# LEDShoeslaces.net
KiCad netlist of a schematic drawn in EAGLE
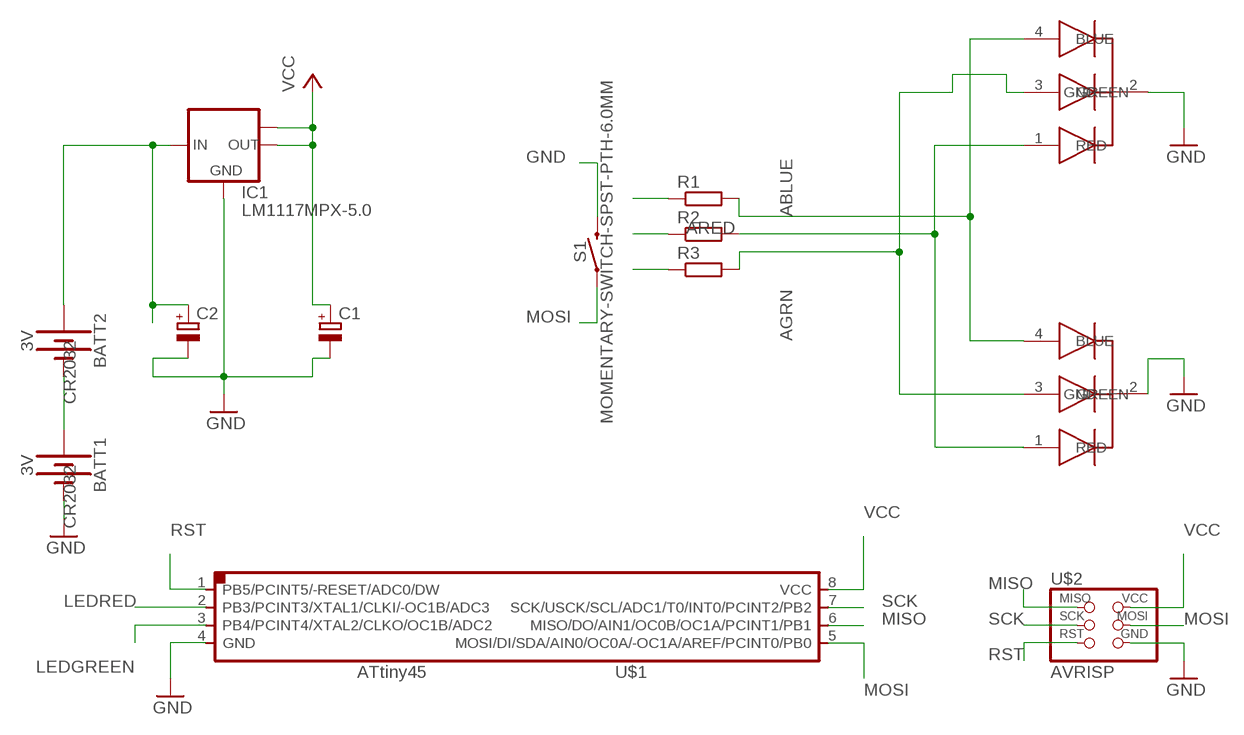
[diagram p0: schematic, sheet 1]

(export (version "E")
  (design (tool "Eeschema 10.0.6"))
  (components
    (comp (ref "BATT1")
      (value "3V")
      (footprint "eagle-import:BATTCON_20MM")
      (fields (field (name "PROD_ID") "BATT-11519") (field (name "PROD_ID_1") "CR2032"))
      (libsource (lib "eagle-import") (part "BATTERY-20MM_SMD"))
    )
    (comp (ref "BATT2")
      (value "3V")
      (footprint "eagle-import:BATTCON_20MM")
      (fields (field (name "PROD_ID") "BATT-11519") (field (name "PROD_ID_1") "CR2032"))
      (libsource (lib "eagle-import") (part "BATTERY-20MM_SMD"))
    )
    (comp (ref "C1")
      (value "CPOL-EUCT7343")
      (footprint "eagle-import:CT7343")
      (libsource (lib "eagle-import") (part "CPOL-EUCT7343"))
    )
    (comp (ref "C2")
      (value "CPOL-EUCT7343")
      (footprint "eagle-import:CT7343")
      (libsource (lib "eagle-import") (part "CPOL-EUCT7343"))
    )
    (comp (ref "IC1")
      (value "LM1117MPX-5.0")
      (footprint "eagle-import:SOT223")
      (libsource (lib "eagle-import") (part "LM1117MPX-5.0"))
    )
    (comp (ref "R1")
      (value "R-EU_R1206")
      (footprint "eagle-import:R1206")
      (libsource (lib "eagle-import") (part "R-EU_R1206"))
    )
    (comp (ref "R2")
      (value "R-EU_R1206")
      (footprint "eagle-import:R1206")
      (libsource (lib "eagle-import") (part "R-EU_R1206"))
    )
    (comp (ref "R3")
      (value "R-EU_R1206")
      (footprint "eagle-import:R1206")
      (libsource (lib "eagle-import") (part "R-EU_R1206"))
    )
    (comp (ref "S1")
      (value "MOMENTARY-SWITCH-SPST-PTH-6.0MM")
      (footprint "eagle-import:TACTILE_SWITCH_PTH_6.0MM")
      (libsource (lib "eagle-import") (part "MOMENTARY-SWITCH-SPST-PTH-6.0MM"))
    )
    (comp (ref "U$1")
      (value "ATTINY45SI")
      (footprint "eagle-import:SOIC8")
      (libsource (lib "eagle-import") (part "ATTINY45SI"))
    )
    (comp (ref "U$2")
      (value "AVRISP")
      (footprint "eagle-import:2X03")
      (libsource (lib "eagle-import") (part "AVRISP"))
    )
    (comp (ref "U$3")
      (value "LEDRGB")
      (footprint "eagle-import:LEDRGB")
      (libsource (lib "eagle-import") (part "LEDRGB"))
    )
    (comp (ref "U$4")
      (value "LEDRGB")
      (footprint "eagle-import:LEDRGB")
      (libsource (lib "eagle-import") (part "LEDRGB"))
    )
  )
  (nets
    (net (code "1") (name "/ABLUE") (class "Default")
      (node (ref "R1") (pin "2") (pinfunction "2_2") (pintype "passive"))
      (node (ref "U$3") (pin "4") (pinfunction "BLUE_4") (pintype "bidirectional"))
      (node (ref "U$4") (pin "4") (pinfunction "BLUE_4") (pintype "bidirectional"))
    )
    (net (code "2") (name "/AGRN") (class "Default")
      (node (ref "R3") (pin "2") (pinfunction "2_2") (pintype "passive"))
      (node (ref "U$3") (pin "3") (pinfunction "GREEN_3") (pintype "bidirectional"))
      (node (ref "U$4") (pin "3") (pinfunction "GREEN_3") (pintype "bidirectional"))
    )
    (net (code "3") (name "/ARED") (class "Default")
      (node (ref "R2") (pin "2") (pinfunction "2_2") (pintype "passive"))
      (node (ref "U$3") (pin "1") (pinfunction "RED_1") (pintype "bidirectional"))
      (node (ref "U$4") (pin "1") (pinfunction "RED_1") (pintype "bidirectional"))
    )
    (net (code "4") (name "/LEDGREEN") (class "Default")
      (node (ref "R3") (pin "1") (pinfunction "1_1") (pintype "passive"))
      (node (ref "U$1") (pin "3") (pinfunction "PB4/PCINT4/XTAL2/CLKO/OC1B/ADC2_3") (pintype "bidirectional"))
    )
    (net (code "5") (name "/LEDRED") (class "Default")
      (node (ref "R1") (pin "1") (pinfunction "1_1") (pintype "passive"))
      (node (ref "U$1") (pin "2") (pinfunction "PB3/PCINT3/XTAL1/CLKI/-OC1B/ADC3_2") (pintype "bidirectional"))
    )
    (net (code "6") (name "/MISO") (class "Default")
      (node (ref "R2") (pin "1") (pinfunction "1_1") (pintype "passive"))
      (node (ref "U$1") (pin "6") (pinfunction "MISO/DO/AIN1/OC0B/OC1A/PCINT1/PB1_6") (pintype "bidirectional"))
      (node (ref "U$2") (pin "1") (pinfunction "MISO_1") (pintype "passive"))
    )
    (net (code "7") (name "/MOSI") (class "Default")
      (node (ref "S1") (pin "1") (pinfunction "1_1") (pintype "passive"))
      (node (ref "U$1") (pin "5") (pinfunction "MOSI/DI/SDA/AIN0/OC0A/-OC1A/AREF/PCINT0/PB0_5") (pintype "bidirectional"))
      (node (ref "U$2") (pin "4") (pinfunction "MOSI_4") (pintype "passive"))
    )
    (net (code "8") (name "/RST") (class "Default")
      (node (ref "U$1") (pin "1") (pinfunction "PB5/PCINT5/-RESET/ADC0/DW_1") (pintype "bidirectional"))
      (node (ref "U$2") (pin "5") (pinfunction "RST_5") (pintype "passive"))
    )
    (net (code "9") (name "/SCK") (class "Default")
      (node (ref "U$1") (pin "7") (pinfunction "SCK/USCK/SCL/ADC1/T0/INT0/PCINT2/PB2_7") (pintype "bidirectional"))
      (node (ref "U$2") (pin "3") (pinfunction "SCK_3") (pintype "passive"))
    )
    (net (code "10") (name "GND") (class "Default")
      (node (ref "BATT1") (pin "2") (pinfunction "-_2") (pintype "power_in"))
      (node (ref "C1") (pin "-") (pinfunction "-_-") (pintype "passive"))
      (node (ref "C2") (pin "-") (pinfunction "-_-") (pintype "passive"))
      (node (ref "IC1") (pin "1") (pinfunction "GND_1") (pintype "input"))
      (node (ref "S1") (pin "3") (pinfunction "2_3") (pintype "passive"))
      (node (ref "U$1") (pin "4") (pinfunction "GND_4") (pintype "bidirectional"))
      (node (ref "U$2") (pin "6") (pinfunction "GND_6") (pintype "passive"))
      (node (ref "U$3") (pin "2") (pinfunction "GND_2") (pintype "bidirectional"))
      (node (ref "U$4") (pin "2") (pinfunction "GND_2") (pintype "bidirectional"))
    )
    (net (code "11") (name "Net-(BATT1-+)") (class "Default")
      (node (ref "BATT1") (pin "1") (pinfunction "+_1") (pintype "power_in"))
      (node (ref "BATT2") (pin "2") (pinfunction "-_2") (pintype "power_in"))
    )
    (net (code "12") (name "Net-(BATT2-+)") (class "Default")
      (node (ref "BATT2") (pin "1") (pinfunction "+_1") (pintype "power_in"))
      (node (ref "C2") (pin "+") (pinfunction "+_+") (pintype "passive"))
      (node (ref "IC1") (pin "3") (pinfunction "IN_3") (pintype "input"))
    )
    (net (code "13") (name "VCC") (class "Default")
      (node (ref "C1") (pin "+") (pinfunction "+_+") (pintype "passive"))
      (node (ref "IC1") (pin "2") (pinfunction "OUT_2") (pintype "passive"))
      (node (ref "IC1") (pin "TAB") (pinfunction "OUT1_TAB") (pintype "passive"))
      (node (ref "U$1") (pin "8") (pinfunction "VCC_8") (pintype "bidirectional"))
      (node (ref "U$2") (pin "2") (pinfunction "VCC_2") (pintype "passive"))
    )
  )
)
